# temp_meter_meas_block.net
KiCad netlist of a schematic drawn in Altium Designer
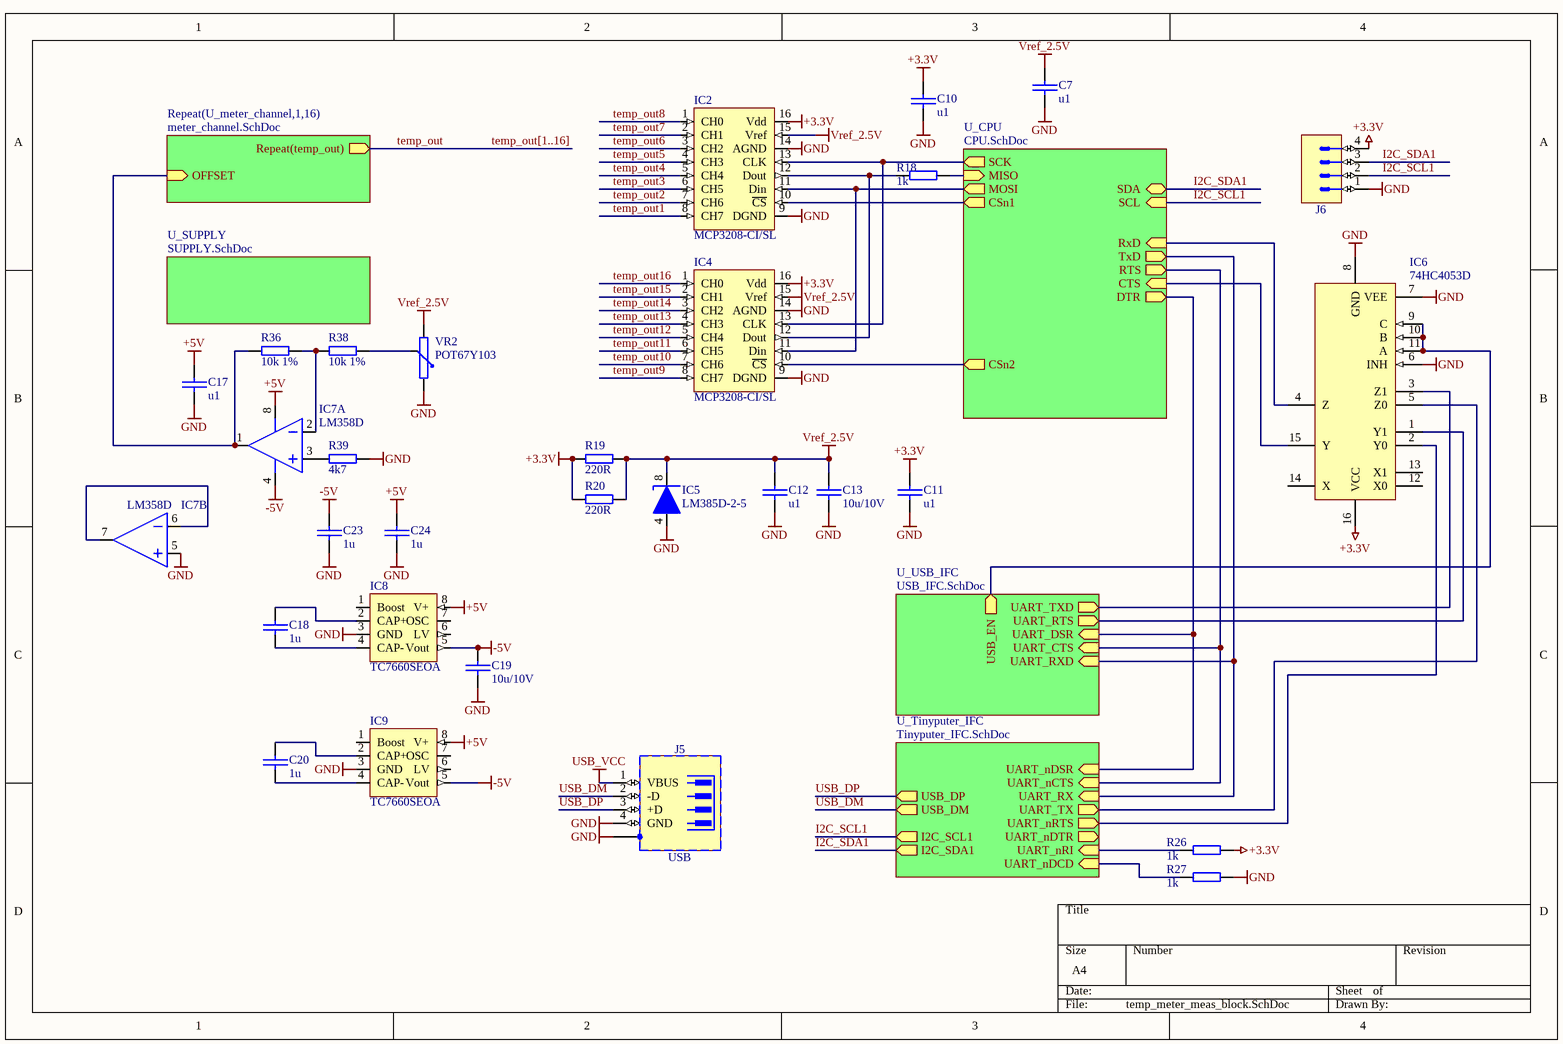
[diagram p0: temp_meter_meas_block.SchDoc]

(export (version "E")
  (design (tool "Eeschema 10.0.6"))
  (components
    (comp (ref "C7")
      (value "u1")
      (footprint "0402C")
      (description "Capacitor SMD")
      (libsource (lib "LIBRARY_SCH") (part "CAP_SMD_0402"))
    )
    (comp (ref "C10")
      (value "u1")
      (footprint "0603C")
      (description "Capacitor SMD")
      (libsource (lib "LIBRARY_SCH") (part "CAP_SMD_0402"))
    )
    (comp (ref "C11")
      (value "u1")
      (footprint "0603C")
      (description "Capacitor SMD")
      (libsource (lib "LIBRARY_SCH") (part "CAP_SMD_0402"))
    )
    (comp (ref "C12")
      (value "u1")
      (footprint "0603C")
      (description "Capacitor SMD")
      (libsource (lib "LIBRARY_SCH") (part "CAP_SMD_0402"))
    )
    (comp (ref "C13")
      (value "10u/10V")
      (footprint "0805C")
      (description "Capacitor SMD")
      (libsource (lib "LIBRARY_SCH") (part "CAP_SMD_0805"))
    )
    (comp (ref "C17")
      (value "u1")
      (footprint "0603C")
      (description "Capacitor SMD")
      (libsource (lib "LIBRARY_SCH") (part "CAP_SMD_0402"))
    )
    (comp (ref "C18")
      (value "1u")
      (footprint "0603C")
      (description "Capacitor SMD")
      (libsource (lib "LIBRARY_SCH") (part "CAP_SMD_0402"))
    )
    (comp (ref "C19")
      (value "10u/10V")
      (footprint "0805C")
      (description "Capacitor SMD")
      (libsource (lib "LIBRARY_SCH") (part "CAP_SMD_0805"))
    )
    (comp (ref "C20")
      (value "1u")
      (footprint "0603C")
      (description "Capacitor SMD")
      (libsource (lib "LIBRARY_SCH") (part "CAP_SMD_0402"))
    )
    (comp (ref "C23")
      (value "1u")
      (footprint "0603C")
      (description "Capacitor SMD")
      (libsource (lib "LIBRARY_SCH") (part "CAP_SMD_0402"))
    )
    (comp (ref "C24")
      (value "1u")
      (footprint "0603C")
      (description "Capacitor SMD")
      (libsource (lib "LIBRARY_SCH") (part "CAP_SMD_0402"))
    )
    (comp (ref "IC2")
      (value "MCP3208-CI/SL")
      (footprint "SO-16")
      (description "8-Channel 12-Bit A/D with SPI")
      (libsource (lib "LIBRARY_SCH") (part "ADC_MCP3208"))
    )
    (comp (ref "IC4")
      (value "MCP3208-CI/SL")
      (footprint "SO-16")
      (description "8-Channel 12-Bit A/D with SPI")
      (libsource (lib "LIBRARY_SCH") (part "ADC_MCP3208"))
    )
    (comp (ref "IC5")
      (value "LM385D-2-5")
      (footprint "SO-8")
      (description "1.2V micropower voltage reference")
      (libsource (lib "LIBRARY_SCH") (part "REF_LM285/385"))
    )
    (comp (ref "IC6") (value "74HC4053D") (footprint "SO-16") (libsource (lib "LIBRARY_SCH") (part "4053")))
    (comp (ref "IC7")
      (value "LM358D")
      (footprint "SO-8")
      (description "Operational Amplifier")
      (libsource (lib "LIBRARY_SCH") (part "OA_LM358"))
    )
    (comp (ref "IC8")
      (value "TC7660SEOA")
      (footprint "SO-8")
      (description "20mA PUMP DC-TO-DC VOLTAGE CONVERTER")
      (libsource (lib "LIBRARY_SCH") (part "PWM_TC7660"))
    )
    (comp (ref "IC9")
      (value "TC7660SEOA")
      (footprint "SO-8")
      (description "20mA PUMP DC-TO-DC VOLTAGE CONVERTER")
      (libsource (lib "LIBRARY_SCH") (part "PWM_TC7660"))
    )
    (comp (ref "J5")
      (value "USB")
      (footprint "FCI_87520-0010BLF")
      (description "4 Pin + 1 Shield USB Receptacle")
      (fields
        (field (name "PART NUMBER") "FCI_87520-0010BLF")
        (field (name "MANUFACTURER") "FCI")
        (field (name "AUTHOR") "CERN DEM JMW")
      )
      (libsource (lib "Connectors") (part "Connector USB 4 Pin + 1Shield"))
    )
    (comp (ref "J6")
      (value "KK®")
      (footprint "MOLEX_22-27-2041")
      (description "Connector 4 Male")
      (fields
        (field (name "PART NUMBER") "MOLEX_22-27-2041")
        (field (name "MANUFACTURER") "MOLEX")
        (field (name "AUTHOR") "CERN DEM JLC")
      )
      (libsource (lib "Connectors") (part "Connector 4 Male"))
    )
    (comp (ref "R18")
      (value "1k")
      (footprint "0603R")
      (description "SMD Resistor")
      (libsource (lib "LIBRARY_SCH") (part "RES_0603"))
    )
    (comp (ref "R19")
      (value "220R")
      (footprint "0805")
      (description "Resistor")
      (libsource (lib "LIBRARY_SCH") (part "RES2"))
    )
    (comp (ref "R20")
      (value "220R")
      (footprint "0805")
      (description "Resistor")
      (libsource (lib "LIBRARY_SCH") (part "RES2"))
    )
    (comp (ref "R26")
      (value "1k")
      (footprint "0603R")
      (description "SMD Resistor")
      (libsource (lib "LIBRARY_SCH") (part "RES_0603"))
    )
    (comp (ref "R27")
      (value "1k")
      (footprint "0603R")
      (description "SMD Resistor")
      (libsource (lib "LIBRARY_SCH") (part "RES_0603"))
    )
    (comp (ref "R36")
      (value "10k 1%")
      (footprint "0603R")
      (description "SMD Resistor")
      (libsource (lib "") (part "RES_0603_1"))
    )
    (comp (ref "R38")
      (value "10k 1%")
      (footprint "0603R")
      (description "SMD Resistor")
      (libsource (lib "") (part "RES_0603_1"))
    )
    (comp (ref "R39")
      (value "4k7")
      (footprint "0603R")
      (description "SMD Resistor")
      (libsource (lib "") (part "RES_0603_1"))
    )
    (comp (ref "VR2")
      (value "POT67Y103")
      (footprint "trimpot1")
      (description "Precision trimpot, 0.5W, +/- 10%")
      (libsource (lib "LIBRARY_SCH") (part "TRIMPOT_PREC_9mm_Y"))
    )
  )
  (nets
    (net (code "1") (name "+3.3V") (class "Default")
      (node (ref "C10") (pin "1") (pinfunction "1_1") (pintype "passive"))
      (node (ref "C11") (pin "1") (pinfunction "1_1") (pintype "passive"))
      (node (ref "IC2") (pin "16") (pinfunction "Vdd_16") (pintype "power_in"))
      (node (ref "IC4") (pin "16") (pinfunction "Vdd_16") (pintype "power_in"))
      (node (ref "IC6") (pin "16") (pinfunction "VCC_16") (pintype "power_in"))
      (node (ref "J6") (pin "4") (pinfunction "4_4") (pintype "bidirectional"))
      (node (ref "R19") (pin "2") (pinfunction "2_2") (pintype "passive"))
      (node (ref "R20") (pin "2") (pinfunction "2_2") (pintype "passive"))
      (node (ref "R26") (pin "2") (pinfunction "2_2") (pintype "passive"))
    )
    (net (code "2") (name "+5V") (class "Default")
      (node (ref "C17") (pin "1") (pinfunction "1_1") (pintype "passive"))
      (node (ref "C24") (pin "1") (pinfunction "1_1") (pintype "passive"))
      (node (ref "IC7") (pin "8") (pinfunction "V+_8") (pintype "passive"))
      (node (ref "IC8") (pin "8") (pinfunction "V+_8") (pintype "input"))
      (node (ref "IC9") (pin "8") (pinfunction "V+_8") (pintype "input"))
    )
    (net (code "3") (name "-5V") (class "Default")
      (node (ref "C19") (pin "1") (pinfunction "1_1") (pintype "passive"))
      (node (ref "C23") (pin "1") (pinfunction "1_1") (pintype "passive"))
      (node (ref "IC7") (pin "4") (pinfunction "V-_4") (pintype "passive"))
      (node (ref "IC8") (pin "5") (pinfunction "Vout_5") (pintype "output"))
      (node (ref "IC9") (pin "5") (pinfunction "Vout_5") (pintype "output"))
    )
    (net (code "4") (name "/CSn1") (class "Default")
      (node (ref "IC2") (pin "10") (pinfunction "~{CS}_10") (pintype "input"))
    )
    (net (code "5") (name "/CSn2") (class "Default")
      (node (ref "IC4") (pin "10") (pinfunction "~{CS}_10") (pintype "input"))
    )
    (net (code "6") (name "/CTS") (class "Default")
      (node (ref "IC6") (pin "15") (pinfunction "Y_15") (pintype "passive"))
    )
    (net (code "8") (name "/I2C_SCL1") (class "Default")
      (node (ref "J6") (pin "2") (pinfunction "2_2") (pintype "bidirectional"))
    )
    (net (code "9") (name "/I2C_SDA1") (class "Default")
      (node (ref "J6") (pin "3") (pinfunction "3_3") (pintype "bidirectional"))
    )
    (net (code "10") (name "/MISO") (class "Default")
      (node (ref "R18") (pin "2") (pinfunction "2_2") (pintype "passive"))
    )
    (net (code "11") (name "/MOSI") (class "Default")
      (node (ref "IC2") (pin "11") (pinfunction "Din_11") (pintype "input"))
      (node (ref "IC4") (pin "11") (pinfunction "Din_11") (pintype "input"))
    )
    (net (code "12") (name "/OFFSET") (class "Default")
      (node (ref "IC7") (pin "1") (pinfunction "OUT_1") (pintype "passive"))
      (node (ref "R36") (pin "1") (pinfunction "1_1") (pintype "passive"))
    )
    (net (code "14") (name "/RxD") (class "Default")
      (node (ref "IC6") (pin "4") (pinfunction "Z_4") (pintype "passive"))
    )
    (net (code "15") (name "/SCK") (class "Default")
      (node (ref "IC2") (pin "13") (pinfunction "CLK_13") (pintype "input"))
      (node (ref "IC4") (pin "13") (pinfunction "CLK_13") (pintype "input"))
    )
    (net (code "17") (name "/UART_RTS") (class "Default")
      (node (ref "IC6") (pin "1") (pinfunction "Y1_1") (pintype "passive"))
    )
    (net (code "18") (name "/UART_TX") (class "Default")
      (node (ref "IC6") (pin "5") (pinfunction "Z0_5") (pintype "passive"))
    )
    (net (code "19") (name "/UART_TXD") (class "Default")
      (node (ref "IC6") (pin "3") (pinfunction "Z1_3") (pintype "passive"))
    )
    (net (code "20") (name "/UART_nDCD") (class "Default")
      (node (ref "R27") (pin "1") (pinfunction "1_1") (pintype "passive"))
    )
    (net (code "22") (name "/UART_nRI") (class "Default")
      (node (ref "R26") (pin "1") (pinfunction "1_1") (pintype "passive"))
    )
    (net (code "23") (name "/UART_nRTS") (class "Default")
      (node (ref "IC6") (pin "2") (pinfunction "Y0_2") (pintype "passive"))
    )
    (net (code "24") (name "/USB_DM") (class "Default")
      (node (ref "J5") (pin "2") (pinfunction "-D_2") (pintype "bidirectional"))
    )
    (net (code "25") (name "/USB_DP") (class "Default")
      (node (ref "J5") (pin "3") (pinfunction "+D_3") (pintype "bidirectional"))
    )
    (net (code "26") (name "/USB_EN") (class "Default")
      (node (ref "IC6") (pin "10") (pinfunction "B_10") (pintype "input"))
      (node (ref "IC6") (pin "11") (pinfunction "A_11") (pintype "input"))
      (node (ref "IC6") (pin "9") (pinfunction "C_9") (pintype "input"))
    )
    (net (code "28") (name "/temp_out1") (class "Default")
      (node (ref "IC2") (pin "8") (pinfunction "CH7_8") (pintype "input"))
    )
    (net (code "29") (name "/temp_out2") (class "Default")
      (node (ref "IC2") (pin "7") (pinfunction "CH6_7") (pintype "input"))
    )
    (net (code "30") (name "/temp_out3") (class "Default")
      (node (ref "IC2") (pin "6") (pinfunction "CH5_6") (pintype "input"))
    )
    (net (code "31") (name "/temp_out4") (class "Default")
      (node (ref "IC2") (pin "5") (pinfunction "CH4_5") (pintype "input"))
    )
    (net (code "32") (name "/temp_out5") (class "Default")
      (node (ref "IC2") (pin "4") (pinfunction "CH3_4") (pintype "input"))
    )
    (net (code "33") (name "/temp_out6") (class "Default")
      (node (ref "IC2") (pin "3") (pinfunction "CH2_3") (pintype "input"))
    )
    (net (code "34") (name "/temp_out7") (class "Default")
      (node (ref "IC2") (pin "2") (pinfunction "CH1_2") (pintype "input"))
    )
    (net (code "35") (name "/temp_out8") (class "Default")
      (node (ref "IC2") (pin "1") (pinfunction "CH0_1") (pintype "input"))
    )
    (net (code "36") (name "/temp_out9") (class "Default")
      (node (ref "IC4") (pin "8") (pinfunction "CH7_8") (pintype "input"))
    )
    (net (code "37") (name "/temp_out10") (class "Default")
      (node (ref "IC4") (pin "7") (pinfunction "CH6_7") (pintype "input"))
    )
    (net (code "38") (name "/temp_out11") (class "Default")
      (node (ref "IC4") (pin "6") (pinfunction "CH5_6") (pintype "input"))
    )
    (net (code "39") (name "/temp_out12") (class "Default")
      (node (ref "IC4") (pin "5") (pinfunction "CH4_5") (pintype "input"))
    )
    (net (code "40") (name "/temp_out13") (class "Default")
      (node (ref "IC4") (pin "4") (pinfunction "CH3_4") (pintype "input"))
    )
    (net (code "41") (name "/temp_out14") (class "Default")
      (node (ref "IC4") (pin "3") (pinfunction "CH2_3") (pintype "input"))
    )
    (net (code "42") (name "/temp_out15") (class "Default")
      (node (ref "IC4") (pin "2") (pinfunction "CH1_2") (pintype "input"))
    )
    (net (code "43") (name "/temp_out16") (class "Default")
      (node (ref "IC4") (pin "1") (pinfunction "CH0_1") (pintype "input"))
    )
    (net (code "45") (name "GND") (class "Default")
      (node (ref "C10") (pin "2") (pinfunction "2_2") (pintype "passive"))
      (node (ref "C11") (pin "2") (pinfunction "2_2") (pintype "passive"))
      (node (ref "C12") (pin "2") (pinfunction "2_2") (pintype "passive"))
      (node (ref "C13") (pin "2") (pinfunction "2_2") (pintype "passive"))
      (node (ref "C17") (pin "2") (pinfunction "2_2") (pintype "passive"))
      (node (ref "C19") (pin "2") (pinfunction "2_2") (pintype "passive"))
      (node (ref "C23") (pin "2") (pinfunction "2_2") (pintype "passive"))
      (node (ref "C24") (pin "2") (pinfunction "2_2") (pintype "passive"))
      (node (ref "C7") (pin "2") (pinfunction "2_2") (pintype "passive"))
      (node (ref "IC2") (pin "14") (pinfunction "AGND_14") (pintype "power_in"))
      (node (ref "IC2") (pin "9") (pinfunction "DGND_9") (pintype "power_in"))
      (node (ref "IC4") (pin "14") (pinfunction "AGND_14") (pintype "power_in"))
      (node (ref "IC4") (pin "9") (pinfunction "DGND_9") (pintype "power_in"))
      (node (ref "IC5") (pin "4") (pinfunction "A_4") (pintype "passive"))
      (node (ref "IC6") (pin "6") (pinfunction "INH_6") (pintype "input"))
      (node (ref "IC6") (pin "7") (pinfunction "VEE_7") (pintype "passive"))
      (node (ref "IC6") (pin "8") (pinfunction "GND_8") (pintype "power_in"))
      (node (ref "IC7") (pin "5") (pinfunction "IN+_5") (pintype "passive"))
      (node (ref "IC8") (pin "3") (pinfunction "GND_3") (pintype "power_in"))
      (node (ref "IC9") (pin "3") (pinfunction "GND_3") (pintype "power_in"))
      (node (ref "J5") (pin "4") (pinfunction "GND_4") (pintype "bidirectional"))
      (node (ref "J5") (pin "5") (pinfunction "SH_5") (pintype "power_in"))
      (node (ref "J6") (pin "1") (pinfunction "1_1") (pintype "bidirectional"))
      (node (ref "R27") (pin "2") (pinfunction "2_2") (pintype "passive"))
      (node (ref "R39") (pin "2") (pinfunction "2_2") (pintype "passive"))
      (node (ref "VR2") (pin "3") (pinfunction "U_3") (pintype "passive"))
    )
    (net (code "46") (name "Net-(IC2-Dout)") (class "Default")
      (node (ref "IC2") (pin "12") (pinfunction "Dout_12") (pintype "output"))
      (node (ref "IC4") (pin "12") (pinfunction "Dout_12") (pintype "output"))
      (node (ref "R18") (pin "1") (pinfunction "1_1") (pintype "passive"))
    )
    (net (code "47") (name "Net-(IC7A-IN+)") (class "Default")
      (node (ref "IC7") (pin "3") (pinfunction "IN+_3") (pintype "passive"))
      (node (ref "R39") (pin "1") (pinfunction "1_1") (pintype "passive"))
    )
    (net (code "48") (name "Net-(IC7A-IN-)") (class "Default")
      (node (ref "IC7") (pin "2") (pinfunction "IN-_2") (pintype "passive"))
      (node (ref "R36") (pin "2") (pinfunction "2_2") (pintype "passive"))
      (node (ref "R38") (pin "1") (pinfunction "1_1") (pintype "passive"))
    )
    (net (code "49") (name "Net-(IC7B-IN-)") (class "Default")
      (node (ref "IC7") (pin "6") (pinfunction "IN-_6") (pintype "passive"))
      (node (ref "IC7") (pin "7") (pinfunction "OUT_7") (pintype "passive"))
    )
    (net (code "50") (name "Net-(IC8-CAP+)") (class "Default")
      (node (ref "C18") (pin "1") (pinfunction "1_1") (pintype "passive"))
      (node (ref "IC8") (pin "2") (pinfunction "CAP+_2") (pintype "passive"))
    )
    (net (code "51") (name "Net-(IC8-CAP-)") (class "Default")
      (node (ref "C18") (pin "2") (pinfunction "2_2") (pintype "passive"))
      (node (ref "IC8") (pin "4") (pinfunction "CAP-_4") (pintype "power_in"))
    )
    (net (code "52") (name "Net-(IC9-CAP+)") (class "Default")
      (node (ref "C20") (pin "1") (pinfunction "1_1") (pintype "passive"))
      (node (ref "IC9") (pin "2") (pinfunction "CAP+_2") (pintype "passive"))
    )
    (net (code "53") (name "Net-(IC9-CAP-)") (class "Default")
      (node (ref "C20") (pin "2") (pinfunction "2_2") (pintype "passive"))
      (node (ref "IC9") (pin "4") (pinfunction "CAP-_4") (pintype "power_in"))
    )
    (net (code "54") (name "Net-(VR2-W)") (class "Default")
      (node (ref "R38") (pin "2") (pinfunction "2_2") (pintype "passive"))
      (node (ref "VR2") (pin "2") (pinfunction "W_2") (pintype "passive"))
    )
    (net (code "55") (name "USB_VCC") (class "Default")
      (node (ref "J5") (pin "1") (pinfunction "VBUS_1") (pintype "bidirectional"))
    )
    (net (code "56") (name "Vref_2.5V") (class "Default")
      (node (ref "C12") (pin "1") (pinfunction "1_1") (pintype "passive"))
      (node (ref "C13") (pin "1") (pinfunction "1_1") (pintype "passive"))
      (node (ref "C7") (pin "1") (pinfunction "1_1") (pintype "passive"))
      (node (ref "IC2") (pin "15") (pinfunction "Vref_15") (pintype "input"))
      (node (ref "IC4") (pin "15") (pinfunction "Vref_15") (pintype "input"))
      (node (ref "IC5") (pin "8") (pinfunction "C_8") (pintype "passive"))
      (node (ref "R19") (pin "1") (pinfunction "1_1") (pintype "passive"))
      (node (ref "R20") (pin "1") (pinfunction "1_1") (pintype "passive"))
      (node (ref "VR2") (pin "1") (pinfunction "D_1") (pintype "passive"))
    )
    (net (code "57") (name "unconnected-(IC6-X-Pad14)") (class "Default")
      (node (ref "IC6") (pin "14") (pinfunction "X_14") (pintype "passive"))
    )
    (net (code "58") (name "unconnected-(IC6-X0-Pad12)") (class "Default")
      (node (ref "IC6") (pin "12") (pinfunction "X0_12") (pintype "passive"))
    )
    (net (code "59") (name "unconnected-(IC6-X1-Pad13)") (class "Default")
      (node (ref "IC6") (pin "13") (pinfunction "X1_13") (pintype "passive"))
    )
    (net (code "60") (name "unconnected-(IC8-Boost-Pad1)") (class "Default")
      (node (ref "IC8") (pin "1") (pinfunction "Boost_1") (pintype "passive"))
    )
    (net (code "61") (name "unconnected-(IC8-LV-Pad6)") (class "Default")
      (node (ref "IC8") (pin "6") (pinfunction "LV_6") (pintype "output"))
    )
    (net (code "62") (name "unconnected-(IC8-OSC-Pad7)") (class "Default")
      (node (ref "IC8") (pin "7") (pinfunction "OSC_7") (pintype "passive"))
    )
    (net (code "63") (name "unconnected-(IC9-Boost-Pad1)") (class "Default")
      (node (ref "IC9") (pin "1") (pinfunction "Boost_1") (pintype "passive"))
    )
    (net (code "64") (name "unconnected-(IC9-LV-Pad6)") (class "Default")
      (node (ref "IC9") (pin "6") (pinfunction "LV_6") (pintype "output"))
    )
    (net (code "65") (name "unconnected-(IC9-OSC-Pad7)") (class "Default")
      (node (ref "IC9") (pin "7") (pinfunction "OSC_7") (pintype "passive"))
    )
  )
)
